# fixture_auto.net
KiCad netlist of a schematic drawn in EAGLE
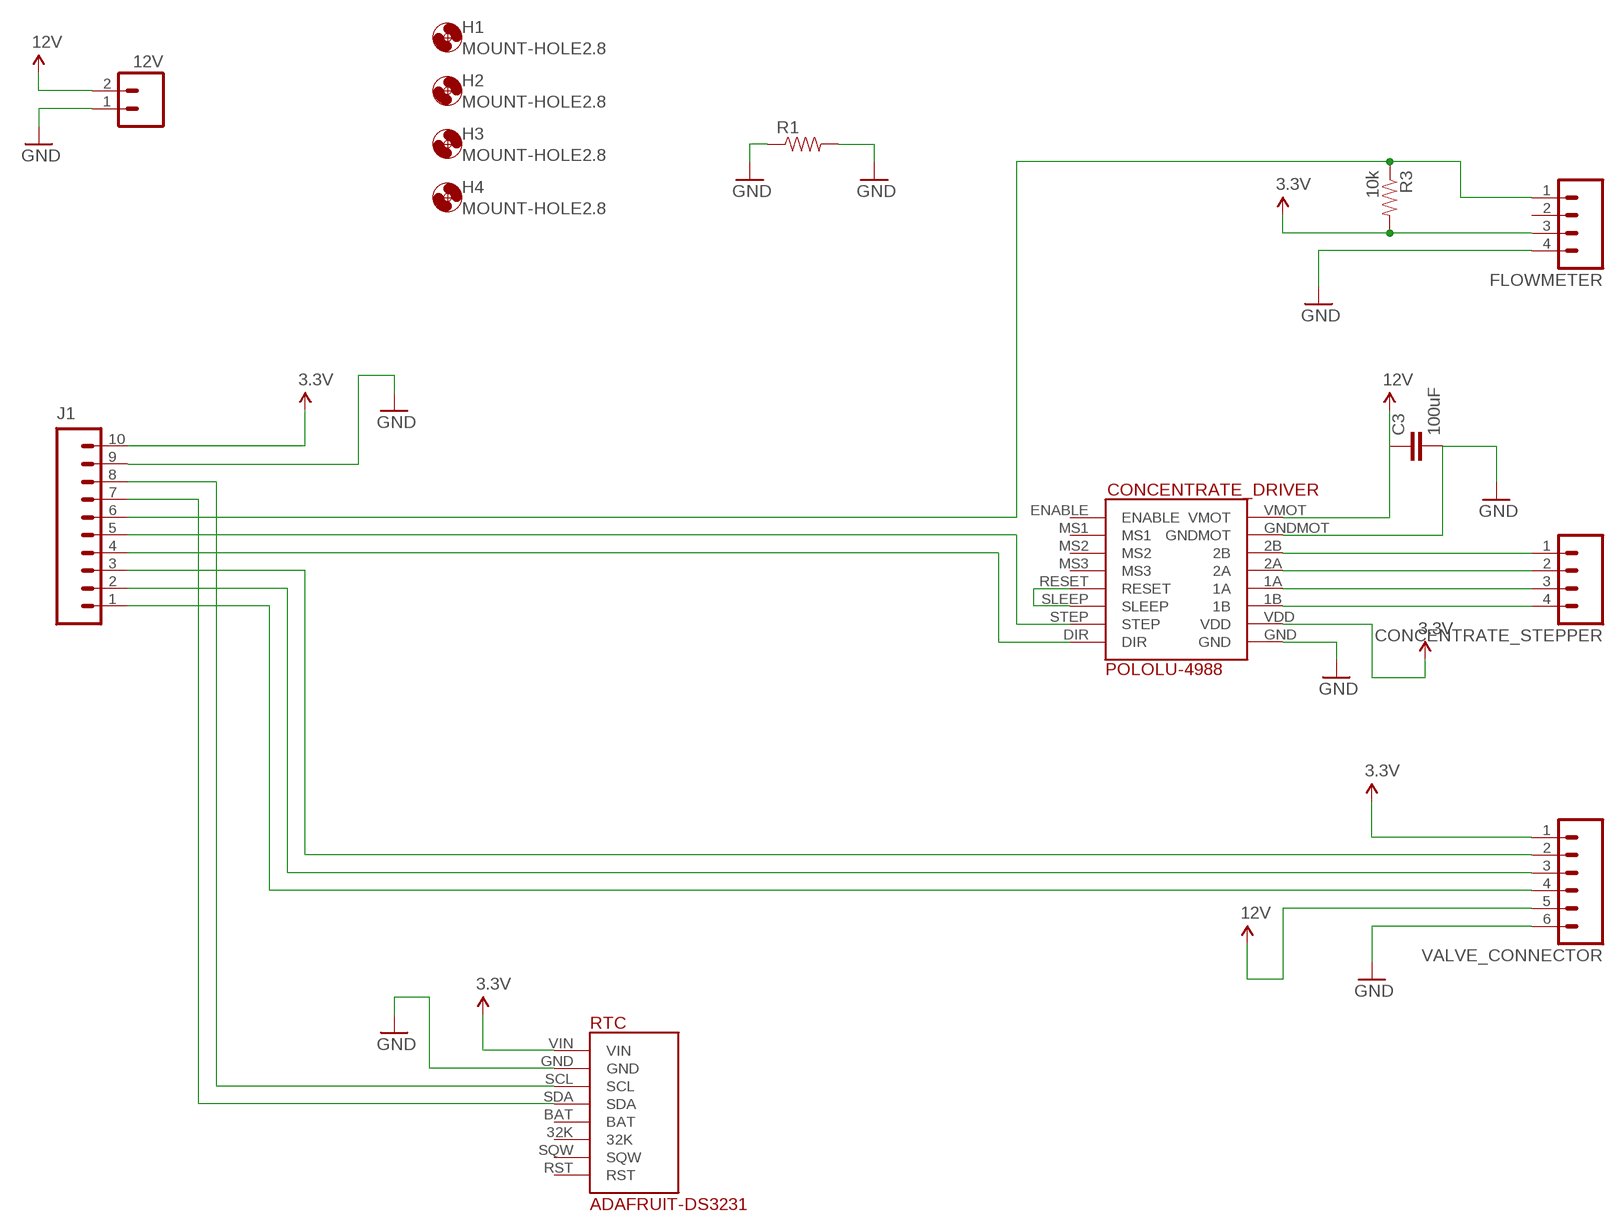
[diagram p0: schematic, sheet 1]

(export (version "E")
  (design (tool "Eeschema 10.0.6"))
  (components
    (comp (ref "12V")
      (value "M02LOCK_LONGPADS")
      (footprint "eagle-import:1X02_LOCK_LONGPADS")
      (libsource (lib "eagle-import") (part "M02LOCK_LONGPADS"))
    )
    (comp (ref "C3")
      (value "100uF")
      (footprint "eagle-import:CAP-PTH-SMALL-KIT")
      (libsource (lib "eagle-import") (part "0.1UF-50V-20%(PTH)KIT-EZ"))
    )
    (comp (ref "CONCENTRATE_DRIVER")
      (value "POLOLU-4988")
      (footprint "eagle-import:POLOLU-4988")
      (libsource (lib "eagle-import") (part "POLOLU-4988"))
    )
    (comp (ref "CONCENTRATE_STEPPER")
      (value "M04LOCK_LONGPADS")
      (footprint "eagle-import:1X04_LOCK_LONGPADS")
      (libsource (lib "eagle-import") (part "M04LOCK_LONGPADS"))
    )
    (comp (ref "FLOWMETER")
      (value "M04LOCK_LONGPADS")
      (footprint "eagle-import:1X04_LOCK_LONGPADS")
      (libsource (lib "eagle-import") (part "M04LOCK_LONGPADS"))
    )
    (comp (ref "H1")
      (value "MOUNT-HOLE2.8")
      (footprint "eagle-import:2,8")
      (libsource (lib "eagle-import") (part "MOUNT-HOLE2.8"))
    )
    (comp (ref "H2")
      (value "MOUNT-HOLE2.8")
      (footprint "eagle-import:2,8")
      (libsource (lib "eagle-import") (part "MOUNT-HOLE2.8"))
    )
    (comp (ref "H3")
      (value "MOUNT-HOLE2.8")
      (footprint "eagle-import:2,8")
      (libsource (lib "eagle-import") (part "MOUNT-HOLE2.8"))
    )
    (comp (ref "H4")
      (value "MOUNT-HOLE2.8")
      (footprint "eagle-import:2,8")
      (libsource (lib "eagle-import") (part "MOUNT-HOLE2.8"))
    )
    (comp (ref "J1")
      (value "M10LOCK_LONGPADS")
      (footprint "eagle-import:1X10_LOCK_LONGPADS")
      (libsource (lib "eagle-import") (part "M10LOCK_LONGPADS"))
    )
    (comp (ref "R1")
      (value "RESISTORPTH-1/2W")
      (footprint "eagle-import:AXIAL-0.5")
      (libsource (lib "eagle-import") (part "SparkFun-Resistors_RESISTORPTH-1/2W"))
    )
    (comp (ref "R3")
      (value "10k")
      (footprint "eagle-import:AXIAL-0.3EZ")
      (libsource (lib "eagle-import") (part "RESISTOREZ"))
    )
    (comp (ref "RTC")
      (value "ADAFRUIT-DS3231")
      (footprint "eagle-import:ADAFRUIT-DS3231")
      (libsource (lib "eagle-import") (part "ADAFRUIT-DS3231"))
    )
    (comp (ref "VALVE_CONNECTOR")
      (value "M06LOCK_LONGPADS")
      (footprint "eagle-import:1X06_LOCK_LONGPADS")
      (libsource (lib "eagle-import") (part "M06LOCK_LONGPADS"))
    )
  )
  (nets
    (net (code "1") (name "3.3V") (class "Default")
      (node (ref "CONCENTRATE_DRIVER") (pin "VDD") (pinfunction "VDD_VDD") (pintype "bidirectional"))
      (node (ref "FLOWMETER") (pin "3") (pinfunction "3_3") (pintype "passive"))
      (node (ref "J1") (pin "10") (pinfunction "10_10") (pintype "passive"))
      (node (ref "R3") (pin "P$2") (pinfunction "2_P$2") (pintype "passive"))
      (node (ref "RTC") (pin "VIN") (pinfunction "VIN_VIN") (pintype "bidirectional"))
      (node (ref "VALVE_CONNECTOR") (pin "1") (pinfunction "1_1") (pintype "passive"))
    )
    (net (code "2") (name "12V") (class "Default")
      (node (ref "12V") (pin "2") (pinfunction "2_2") (pintype "passive"))
      (node (ref "C3") (pin "1") (pinfunction "1_1") (pintype "passive"))
      (node (ref "CONCENTRATE_DRIVER") (pin "VMOT") (pinfunction "VMOT_VMOT") (pintype "bidirectional"))
      (node (ref "VALVE_CONNECTOR") (pin "5") (pinfunction "5_5") (pintype "passive"))
    )
    (net (code "3") (name "GND") (class "Default")
      (node (ref "12V") (pin "1") (pinfunction "1_1") (pintype "passive"))
      (node (ref "C3") (pin "2") (pinfunction "2_2") (pintype "passive"))
      (node (ref "CONCENTRATE_DRIVER") (pin "GND") (pinfunction "GND_GND") (pintype "bidirectional"))
      (node (ref "CONCENTRATE_DRIVER") (pin "GNDMOT") (pinfunction "GNDMOT_GNDMOT") (pintype "bidirectional"))
      (node (ref "FLOWMETER") (pin "4") (pinfunction "4_4") (pintype "passive"))
      (node (ref "J1") (pin "9") (pinfunction "9_9") (pintype "passive"))
      (node (ref "R1") (pin "P$1") (pinfunction "1_P$1") (pintype "passive"))
      (node (ref "R1") (pin "P$2") (pinfunction "2_P$2") (pintype "passive"))
      (node (ref "RTC") (pin "GND") (pinfunction "GND_GND") (pintype "bidirectional"))
      (node (ref "VALVE_CONNECTOR") (pin "6") (pinfunction "6_6") (pintype "passive"))
    )
    (net (code "4") (name "Net-(CONCENTRATE_DRIVER-Pad1A)") (class "Default")
      (node (ref "CONCENTRATE_DRIVER") (pin "1A") (pinfunction "1A_1A") (pintype "bidirectional"))
      (node (ref "CONCENTRATE_STEPPER") (pin "3") (pinfunction "3_3") (pintype "passive"))
    )
    (net (code "5") (name "Net-(CONCENTRATE_DRIVER-Pad1B)") (class "Default")
      (node (ref "CONCENTRATE_DRIVER") (pin "1B") (pinfunction "1B_1B") (pintype "bidirectional"))
      (node (ref "CONCENTRATE_STEPPER") (pin "4") (pinfunction "4_4") (pintype "passive"))
    )
    (net (code "6") (name "Net-(CONCENTRATE_DRIVER-Pad2A)") (class "Default")
      (node (ref "CONCENTRATE_DRIVER") (pin "2A") (pinfunction "2A_2A") (pintype "bidirectional"))
      (node (ref "CONCENTRATE_STEPPER") (pin "2") (pinfunction "2_2") (pintype "passive"))
    )
    (net (code "7") (name "Net-(CONCENTRATE_DRIVER-Pad2B)") (class "Default")
      (node (ref "CONCENTRATE_DRIVER") (pin "2B") (pinfunction "2B_2B") (pintype "bidirectional"))
      (node (ref "CONCENTRATE_STEPPER") (pin "1") (pinfunction "1_1") (pintype "passive"))
    )
    (net (code "8") (name "Net-(CONCENTRATE_DRIVER-PadDIR)") (class "Default")
      (node (ref "CONCENTRATE_DRIVER") (pin "DIR") (pinfunction "DIR_DIR") (pintype "bidirectional"))
      (node (ref "J1") (pin "4") (pinfunction "4_4") (pintype "passive"))
    )
    (net (code "9") (name "Net-(CONCENTRATE_DRIVER-PadRESET)") (class "Default")
      (node (ref "CONCENTRATE_DRIVER") (pin "RESET") (pinfunction "RESET_RESET") (pintype "bidirectional"))
      (node (ref "CONCENTRATE_DRIVER") (pin "SLEEP") (pinfunction "SLEEP_SLEEP") (pintype "bidirectional"))
    )
    (net (code "10") (name "Net-(CONCENTRATE_DRIVER-PadSTEP)") (class "Default")
      (node (ref "CONCENTRATE_DRIVER") (pin "STEP") (pinfunction "STEP_STEP") (pintype "bidirectional"))
      (node (ref "J1") (pin "5") (pinfunction "5_5") (pintype "passive"))
    )
    (net (code "11") (name "Net-(J1-Pad1)") (class "Default")
      (node (ref "J1") (pin "1") (pinfunction "1_1") (pintype "passive"))
      (node (ref "VALVE_CONNECTOR") (pin "4") (pinfunction "4_4") (pintype "passive"))
    )
    (net (code "12") (name "Net-(J1-Pad2)") (class "Default")
      (node (ref "J1") (pin "2") (pinfunction "2_2") (pintype "passive"))
      (node (ref "VALVE_CONNECTOR") (pin "3") (pinfunction "3_3") (pintype "passive"))
    )
    (net (code "13") (name "Net-(J1-Pad3)") (class "Default")
      (node (ref "J1") (pin "3") (pinfunction "3_3") (pintype "passive"))
      (node (ref "VALVE_CONNECTOR") (pin "2") (pinfunction "2_2") (pintype "passive"))
    )
    (net (code "14") (name "Net-(J1-Pad7)") (class "Default")
      (node (ref "J1") (pin "7") (pinfunction "7_7") (pintype "passive"))
      (node (ref "RTC") (pin "SDA") (pinfunction "SDA_SDA") (pintype "bidirectional"))
    )
    (net (code "15") (name "Net-(J1-Pad8)") (class "Default")
      (node (ref "J1") (pin "8") (pinfunction "8_8") (pintype "passive"))
      (node (ref "RTC") (pin "SCL") (pinfunction "SCL_SCL") (pintype "bidirectional"))
    )
    (net (code "16") (name "Net-(R3-1)") (class "Default")
      (node (ref "FLOWMETER") (pin "1") (pinfunction "1_1") (pintype "passive"))
      (node (ref "J1") (pin "6") (pinfunction "6_6") (pintype "passive"))
      (node (ref "R3") (pin "P$1") (pinfunction "1_P$1") (pintype "passive"))
    )
    (net (code "17") (name "unconnected-(CONCENTRATE_DRIVER-PadENABLE)") (class "Default")
      (node (ref "CONCENTRATE_DRIVER") (pin "ENABLE") (pinfunction "ENABLE_ENABLE") (pintype "bidirectional"))
    )
    (net (code "18") (name "unconnected-(CONCENTRATE_DRIVER-PadMS1)") (class "Default")
      (node (ref "CONCENTRATE_DRIVER") (pin "MS1") (pinfunction "MS1_MS1") (pintype "bidirectional"))
    )
    (net (code "19") (name "unconnected-(CONCENTRATE_DRIVER-PadMS2)") (class "Default")
      (node (ref "CONCENTRATE_DRIVER") (pin "MS2") (pinfunction "MS2_MS2") (pintype "bidirectional"))
    )
    (net (code "20") (name "unconnected-(CONCENTRATE_DRIVER-PadMS3)") (class "Default")
      (node (ref "CONCENTRATE_DRIVER") (pin "MS3") (pinfunction "MS3_MS3") (pintype "bidirectional"))
    )
    (net (code "21") (name "unconnected-(FLOWMETER-Pad2)") (class "Default")
      (node (ref "FLOWMETER") (pin "2") (pinfunction "2_2") (pintype "passive"))
    )
    (net (code "22") (name "unconnected-(RTC-Pad32K)") (class "Default")
      (node (ref "RTC") (pin "32K") (pinfunction "32K_32K") (pintype "bidirectional"))
    )
    (net (code "23") (name "unconnected-(RTC-PadBAT)") (class "Default")
      (node (ref "RTC") (pin "BAT") (pinfunction "BAT_BAT") (pintype "bidirectional"))
    )
    (net (code "24") (name "unconnected-(RTC-PadRST)") (class "Default")
      (node (ref "RTC") (pin "RST") (pinfunction "RST_RST") (pintype "bidirectional"))
    )
    (net (code "25") (name "unconnected-(RTC-PadSQW)") (class "Default")
      (node (ref "RTC") (pin "SQW") (pinfunction "SQW_SQW") (pintype "bidirectional"))
    )
  )
)
